# SCH_task_B_2026-06-26.net
KiCad netlist of a schematic drawn in EasyEDA
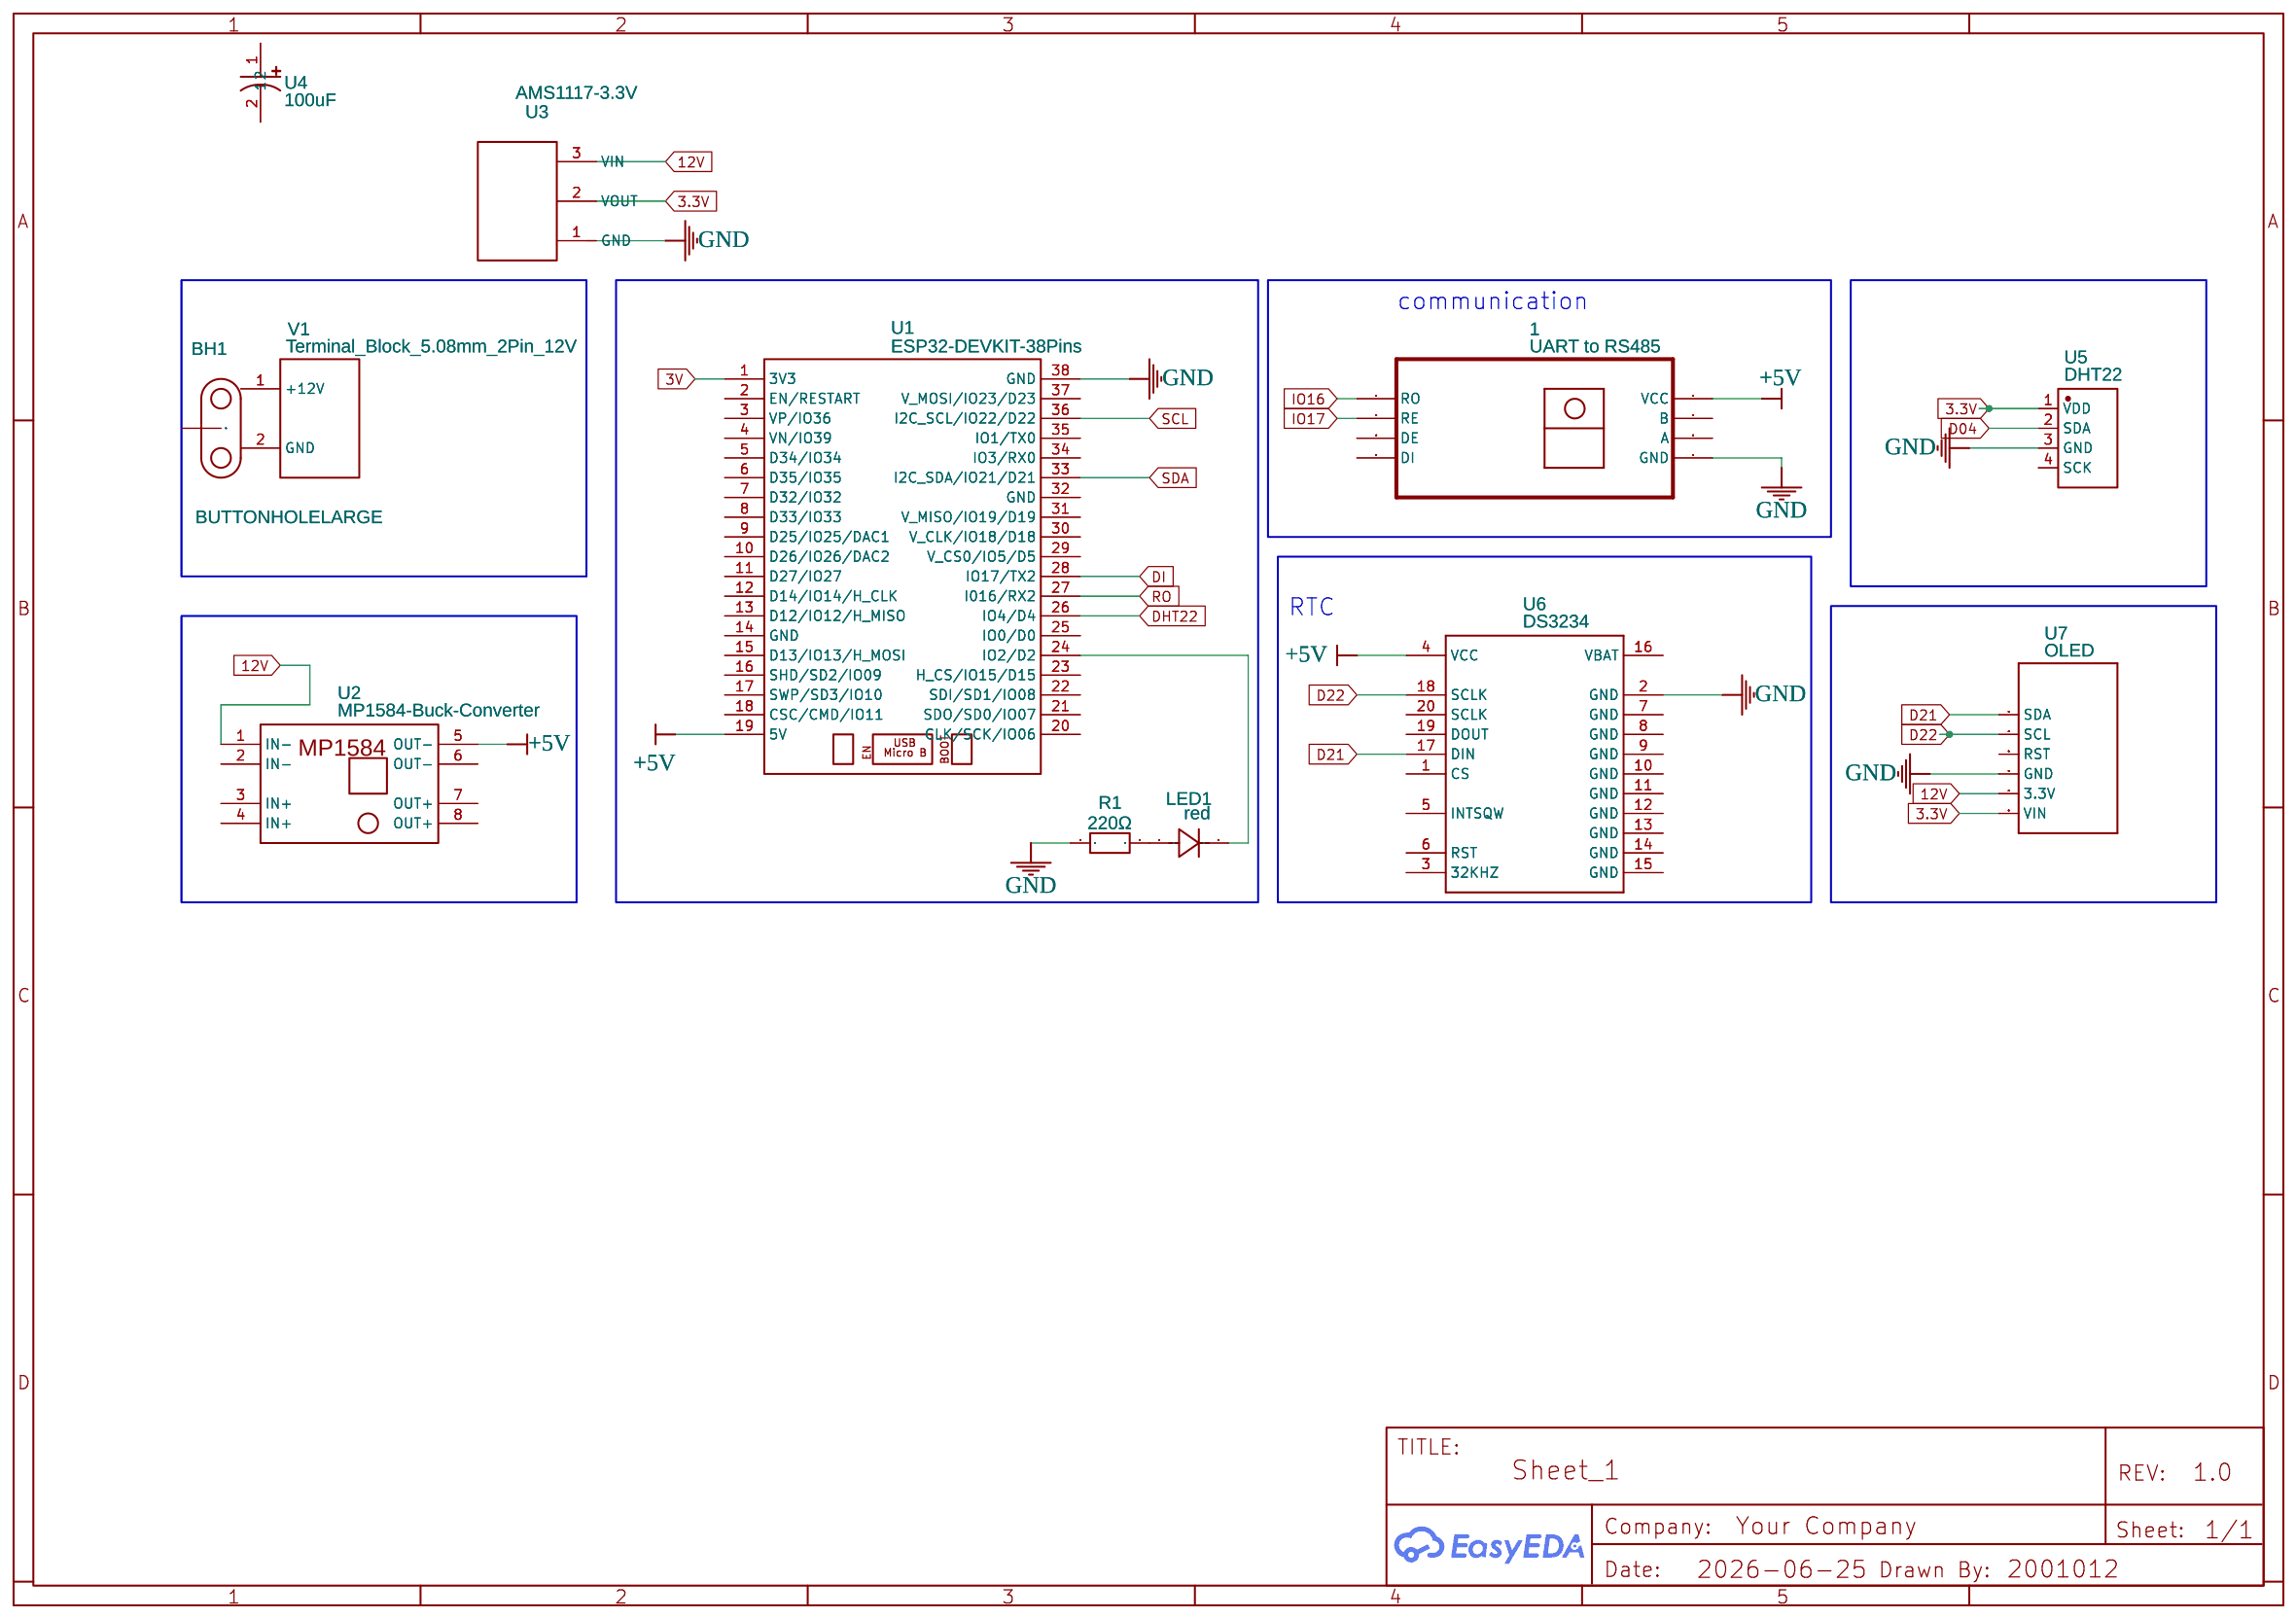
[diagram p0: schematic sheet]

(export (version "E")
  (design (tool "Eeschema 10.0.6"))
  (components
    (comp (ref "1") (value "UART to RS485") (libsource (lib "") (part "UART to RS485")))
    (comp (ref "BH1") (value "BUTTONHOLELARGE") (libsource (lib "") (part "BUTTONHOLELARGE")))
    (comp (ref "LED1")
      (value "red")
      (fields (field (name "Manufacturer Part") "YLED0402O") (field (name "Manufacturer") "YONGYUTAI(永裕泰)"))
      (libsource (lib "") (part "YLED0402O"))
    )
    (comp (ref "R1")
      (value "220Ω")
      (fields (field (name "Manufacturer Part") "RWS10 220R J TR") (field (name "Manufacturer") "Ohmite"))
      (libsource (lib "") (part "RWS10 220R J TR"))
    )
    (comp (ref "U1") (value "ESP32-DEVKIT-38Pins") (libsource (lib "") (part "ESP32-DEVKIT-38Pins")))
    (comp (ref "U2")
      (value "MP1584-Buck-Converter")
      (fields (field (name "Manufacturer Part") "MP1584EN"))
      (libsource (lib "") (part "MP1584-Buck-Converter"))
    )
    (comp (ref "U3") (value "AMS1117-3.3V") (libsource (lib "") (part "AMS1117-3.3V")))
    (comp (ref "U4")
      (value "100uF")
      (fields
        (field (name "Manufacturer Part") "6.3NA100MEFC5X11")
        (field (name "Manufacturer") "rubycon(红宝石)")
      )
      (libsource (lib "") (part "100UF-D5XL11MM-HORN-TYPE-POLAR-ELECTROLYTIC-CAPACITORS COPY"))
    )
    (comp (ref "U5")
      (value "DHT22")
      (fields (field (name "Manufacturer") "HAIGU(广州海谷)"))
      (libsource (lib "") (part "DHT22"))
    )
    (comp (ref "U6") (value "DS3234") (libsource (lib "") (part "DS3234")))
    (comp (ref "U7") (value "OLED") (libsource (lib "") (part "ADAFRUIT_128X32_OLED")))
    (comp (ref "V1")
      (value "Terminal_Block_5.08mm_2Pin_12V")
      (libsource (lib "") (part "Terminal_Block_5.08mm_2Pin_12V"))
    )
  )
  (nets
    (net (code "1") (name "+5V") (class "Default")
      (node (ref "1") (pin "RS5") (pinfunction "VCC_RS5") (pintype "bidirectional"))
      (node (ref "U1") (pin "19") (pinfunction "5V_19") (pintype "unspecified"))
      (node (ref "U2") (pin "5") (pinfunction "OUT-_5") (pintype "unspecified"))
      (node (ref "U6") (pin "4") (pinfunction "VCC_4") (pintype "unspecified"))
    )
    (net (code "2") (name "3.3V") (class "Default")
      (node (ref "U5") (pin "1") (pinfunction "VDD_1") (pintype "unspecified"))
      (node (ref "U7") (pin "P$6") (pinfunction "VIN_P$6") (pintype "passive"))
    )
    (net (code "3") (name "3V") (class "Default")
      (node (ref "U1") (pin "1") (pinfunction "3V3_1") (pintype "unspecified"))
    )
    (net (code "4") (name "12V") (class "Default")
      (node (ref "U2") (pin "1") (pinfunction "IN-_1") (pintype "unspecified"))
      (node (ref "U7") (pin "P$5") (pinfunction "3.3V_P$5") (pintype "passive"))
    )
    (net (code "5") (name "D04") (class "Default")
      (node (ref "U5") (pin "2") (pinfunction "SDA_2") (pintype "unspecified"))
    )
    (net (code "6") (name "D21") (class "Default")
      (node (ref "U6") (pin "17") (pinfunction "DIN_17") (pintype "unspecified"))
      (node (ref "U7") (pin "P$1") (pinfunction "SDA_P$1") (pintype "unspecified"))
    )
    (net (code "7") (name "D22") (class "Default")
      (node (ref "U6") (pin "18") (pinfunction "SCLK_18") (pintype "unspecified"))
      (node (ref "U7") (pin "P$2") (pinfunction "SCL_P$2") (pintype "unspecified"))
    )
    (net (code "8") (name "DHT22") (class "Default")
      (node (ref "U1") (pin "26") (pinfunction "IO4/D4_26") (pintype "unspecified"))
    )
    (net (code "9") (name "DI") (class "Default")
      (node (ref "U1") (pin "28") (pinfunction "IO17/TX2_28") (pintype "unspecified"))
    )
    (net (code "10") (name "GND") (class "Default")
      (node (ref "1") (pin "RS8") (pinfunction "GND_RS8") (pintype "bidirectional"))
      (node (ref "R1") (pin "1") (pinfunction "1_1") (pintype "unspecified"))
      (node (ref "U1") (pin "38") (pinfunction "GND_38") (pintype "unspecified"))
      (node (ref "U5") (pin "3") (pinfunction "GND_3") (pintype "unspecified"))
      (node (ref "U6") (pin "2") (pinfunction "GND_2") (pintype "unspecified"))
      (node (ref "U7") (pin "P$4") (pinfunction "GND_P$4") (pintype "passive"))
    )
    (net (code "11") (name "IO16") (class "Default")
      (node (ref "1") (pin "RS1") (pinfunction "RO_RS1") (pintype "bidirectional"))
    )
    (net (code "12") (name "IO17") (class "Default")
      (node (ref "1") (pin "RS2") (pinfunction "RE_RS2") (pintype "bidirectional"))
    )
    (net (code "13") (name "Net-(LED1-A)") (class "Default")
      (node (ref "LED1") (pin "1") (pinfunction "A_1") (pintype "unspecified"))
      (node (ref "R1") (pin "2") (pinfunction "2_2") (pintype "unspecified"))
    )
    (net (code "14") (name "Net-(LED1-C)") (class "Default")
      (node (ref "LED1") (pin "2") (pinfunction "C_2") (pintype "unspecified"))
      (node (ref "U1") (pin "24") (pinfunction "IO2/D2_24") (pintype "unspecified"))
    )
    (net (code "15") (name "RO") (class "Default")
      (node (ref "U1") (pin "27") (pinfunction "I016/RX2_27") (pintype "unspecified"))
    )
    (net (code "16") (name "SCL") (class "Default")
      (node (ref "U1") (pin "36") (pinfunction "I2C_SCL/IO22/D22_36") (pintype "unspecified"))
    )
    (net (code "17") (name "SDA") (class "Default")
      (node (ref "U1") (pin "33") (pinfunction "I2C_SDA/IO21/D21_33") (pintype "unspecified"))
    )
    (net (code "18") (name "unconnected-(1-A-PadRS7)") (class "Default")
      (node (ref "1") (pin "RS7") (pinfunction "A_RS7") (pintype "bidirectional"))
    )
    (net (code "19") (name "unconnected-(1-B-PadRS6)") (class "Default")
      (node (ref "1") (pin "RS6") (pinfunction "B_RS6") (pintype "bidirectional"))
    )
    (net (code "20") (name "unconnected-(1-DE-PadRS3)") (class "Default")
      (node (ref "1") (pin "RS3") (pinfunction "DE_RS3") (pintype "bidirectional"))
    )
    (net (code "21") (name "unconnected-(1-DI-PadRS4)") (class "Default")
      (node (ref "1") (pin "RS4") (pinfunction "DI_RS4") (pintype "bidirectional"))
    )
    (net (code "22") (name "unconnected-(BH1-PadP$1)") (class "Default")
      (node (ref "BH1") (pin "P$1") (pinfunction "P$1_P$1") (pintype "unspecified"))
    )
    (net (code "23") (name "unconnected-(U1-CLK{slash}SCK{slash}IO06-Pad20)") (class "Default")
      (node (ref "U1") (pin "20") (pinfunction "CLK/SCK/IO06_20") (pintype "unspecified"))
    )
    (net (code "24") (name "unconnected-(U1-CSC{slash}CMD{slash}IO11-Pad18)") (class "Default")
      (node (ref "U1") (pin "18") (pinfunction "CSC/CMD/IO11_18") (pintype "unspecified"))
    )
    (net (code "25") (name "unconnected-(U1-D12{slash}IO12{slash}H_MISO-Pad13)") (class "Default")
      (node (ref "U1") (pin "13") (pinfunction "D12/IO12/H_MISO_13") (pintype "unspecified"))
    )
    (net (code "26") (name "unconnected-(U1-D13{slash}IO13{slash}H_MOSI-Pad15)") (class "Default")
      (node (ref "U1") (pin "15") (pinfunction "D13/IO13/H_MOSI_15") (pintype "unspecified"))
    )
    (net (code "27") (name "unconnected-(U1-D14{slash}IO14{slash}H_CLK-Pad12)") (class "Default")
      (node (ref "U1") (pin "12") (pinfunction "D14/IO14/H_CLK_12") (pintype "unspecified"))
    )
    (net (code "28") (name "unconnected-(U1-D25{slash}IO25{slash}DAC1-Pad9)") (class "Default")
      (node (ref "U1") (pin "9") (pinfunction "D25/IO25/DAC1_9") (pintype "unspecified"))
    )
    (net (code "29") (name "unconnected-(U1-D26{slash}IO26{slash}DAC2-Pad10)") (class "Default")
      (node (ref "U1") (pin "10") (pinfunction "D26/IO26/DAC2_10") (pintype "unspecified"))
    )
    (net (code "30") (name "unconnected-(U1-D27{slash}IO27-Pad11)") (class "Default")
      (node (ref "U1") (pin "11") (pinfunction "D27/IO27_11") (pintype "unspecified"))
    )
    (net (code "31") (name "unconnected-(U1-D32{slash}IO32-Pad7)") (class "Default")
      (node (ref "U1") (pin "7") (pinfunction "D32/IO32_7") (pintype "unspecified"))
    )
    (net (code "32") (name "unconnected-(U1-D33{slash}IO33-Pad8)") (class "Default")
      (node (ref "U1") (pin "8") (pinfunction "D33/IO33_8") (pintype "unspecified"))
    )
    (net (code "33") (name "unconnected-(U1-D34{slash}IO34-Pad5)") (class "Default")
      (node (ref "U1") (pin "5") (pinfunction "D34/IO34_5") (pintype "unspecified"))
    )
    (net (code "34") (name "unconnected-(U1-D35{slash}IO35-Pad6)") (class "Default")
      (node (ref "U1") (pin "6") (pinfunction "D35/IO35_6") (pintype "unspecified"))
    )
    (net (code "35") (name "unconnected-(U1-EN{slash}RESTART-Pad2)") (class "Default")
      (node (ref "U1") (pin "2") (pinfunction "EN/RESTART_2") (pintype "unspecified"))
    )
    (net (code "36") (name "unconnected-(U1-GND-Pad14)") (class "Default")
      (node (ref "U1") (pin "14") (pinfunction "GND_14") (pintype "unspecified"))
    )
    (net (code "37") (name "unconnected-(U1-GND-Pad32)") (class "Default")
      (node (ref "U1") (pin "32") (pinfunction "GND_32") (pintype "unspecified"))
    )
    (net (code "38") (name "unconnected-(U1-H_CS{slash}IO15{slash}D15-Pad23)") (class "Default")
      (node (ref "U1") (pin "23") (pinfunction "H_CS/IO15/D15_23") (pintype "unspecified"))
    )
    (net (code "39") (name "unconnected-(U1-IO0{slash}D0-Pad25)") (class "Default")
      (node (ref "U1") (pin "25") (pinfunction "IO0/D0_25") (pintype "unspecified"))
    )
    (net (code "40") (name "unconnected-(U1-IO1{slash}TX0-Pad35)") (class "Default")
      (node (ref "U1") (pin "35") (pinfunction "IO1/TX0_35") (pintype "unspecified"))
    )
    (net (code "41") (name "unconnected-(U1-IO3{slash}RX0-Pad34)") (class "Default")
      (node (ref "U1") (pin "34") (pinfunction "IO3/RX0_34") (pintype "unspecified"))
    )
    (net (code "42") (name "unconnected-(U1-SDI{slash}SD1{slash}IO08-Pad22)") (class "Default")
      (node (ref "U1") (pin "22") (pinfunction "SDI/SD1/IO08_22") (pintype "unspecified"))
    )
    (net (code "43") (name "unconnected-(U1-SDO{slash}SD0{slash}IO07-Pad21)") (class "Default")
      (node (ref "U1") (pin "21") (pinfunction "SDO/SD0/IO07_21") (pintype "unspecified"))
    )
    (net (code "44") (name "unconnected-(U1-SHD{slash}SD2{slash}IO09-Pad16)") (class "Default")
      (node (ref "U1") (pin "16") (pinfunction "SHD/SD2/IO09_16") (pintype "unspecified"))
    )
    (net (code "45") (name "unconnected-(U1-SWP{slash}SD3{slash}IO10-Pad17)") (class "Default")
      (node (ref "U1") (pin "17") (pinfunction "SWP/SD3/IO10_17") (pintype "unspecified"))
    )
    (net (code "46") (name "unconnected-(U1-VN{slash}IO39-Pad4)") (class "Default")
      (node (ref "U1") (pin "4") (pinfunction "VN/IO39_4") (pintype "unspecified"))
    )
    (net (code "47") (name "unconnected-(U1-VP{slash}IO36-Pad3)") (class "Default")
      (node (ref "U1") (pin "3") (pinfunction "VP/IO36_3") (pintype "unspecified"))
    )
    (net (code "48") (name "unconnected-(U1-V_CLK{slash}IO18{slash}D18-Pad30)") (class "Default")
      (node (ref "U1") (pin "30") (pinfunction "V_CLK/IO18/D18_30") (pintype "unspecified"))
    )
    (net (code "49") (name "unconnected-(U1-V_CS0{slash}IO5{slash}D5-Pad29)") (class "Default")
      (node (ref "U1") (pin "29") (pinfunction "V_CS0/IO5/D5_29") (pintype "unspecified"))
    )
    (net (code "50") (name "unconnected-(U1-V_MISO{slash}IO19{slash}D19-Pad31)") (class "Default")
      (node (ref "U1") (pin "31") (pinfunction "V_MISO/IO19/D19_31") (pintype "unspecified"))
    )
    (net (code "51") (name "unconnected-(U1-V_MOSI{slash}IO23{slash}D23-Pad37)") (class "Default")
      (node (ref "U1") (pin "37") (pinfunction "V_MOSI/IO23/D23_37") (pintype "unspecified"))
    )
    (net (code "52") (name "unconnected-(U2-IN+-Pad3)") (class "Default")
      (node (ref "U2") (pin "3") (pinfunction "IN+_3") (pintype "unspecified"))
    )
    (net (code "53") (name "unconnected-(U2-IN+-Pad4)") (class "Default")
      (node (ref "U2") (pin "4") (pinfunction "IN+_4") (pintype "unspecified"))
    )
    (net (code "54") (name "unconnected-(U2-IN--Pad2)") (class "Default")
      (node (ref "U2") (pin "2") (pinfunction "IN-_2") (pintype "unspecified"))
    )
    (net (code "55") (name "unconnected-(U2-OUT+-Pad7)") (class "Default")
      (node (ref "U2") (pin "7") (pinfunction "OUT+_7") (pintype "unspecified"))
    )
    (net (code "56") (name "unconnected-(U2-OUT+-Pad8)") (class "Default")
      (node (ref "U2") (pin "8") (pinfunction "OUT+_8") (pintype "unspecified"))
    )
    (net (code "57") (name "unconnected-(U2-OUT--Pad6)") (class "Default")
      (node (ref "U2") (pin "6") (pinfunction "OUT-_6") (pintype "unspecified"))
    )
    (net (code "58") (name "unconnected-(U3-GND-Pad1)") (class "Default")
      (node (ref "U3") (pin "1") (pinfunction "GND_1") (pintype "unspecified"))
    )
    (net (code "59") (name "unconnected-(U3-VIN-Pad3)") (class "Default")
      (node (ref "U3") (pin "3") (pinfunction "VIN_3") (pintype "unspecified"))
    )
    (net (code "60") (name "unconnected-(U3-VOUT-Pad2)") (class "Default")
      (node (ref "U3") (pin "2") (pinfunction "VOUT_2") (pintype "unspecified"))
    )
    (net (code "61") (name "unconnected-(U4-Pad1)") (class "Default")
      (node (ref "U4") (pin "1") (pinfunction "1_1") (pintype "unspecified"))
    )
    (net (code "62") (name "unconnected-(U4-Pad2)") (class "Default")
      (node (ref "U4") (pin "2") (pinfunction "2_2") (pintype "unspecified"))
    )
    (net (code "63") (name "unconnected-(U5-SCK-Pad4)") (class "Default")
      (node (ref "U5") (pin "4") (pinfunction "SCK_4") (pintype "unspecified"))
    )
    (net (code "64") (name "unconnected-(U6-32KHZ-Pad3)") (class "Default")
      (node (ref "U6") (pin "3") (pinfunction "32KHZ_3") (pintype "unspecified"))
    )
    (net (code "65") (name "unconnected-(U6-CS-Pad1)") (class "Default")
      (node (ref "U6") (pin "1") (pinfunction "CS_1") (pintype "unspecified"))
    )
    (net (code "66") (name "unconnected-(U6-DOUT-Pad19)") (class "Default")
      (node (ref "U6") (pin "19") (pinfunction "DOUT_19") (pintype "unspecified"))
    )
    (net (code "67") (name "unconnected-(U6-GND-Pad7)") (class "Default")
      (node (ref "U6") (pin "7") (pinfunction "GND_7") (pintype "unspecified"))
    )
    (net (code "68") (name "unconnected-(U6-GND-Pad8)") (class "Default")
      (node (ref "U6") (pin "8") (pinfunction "GND_8") (pintype "unspecified"))
    )
    (net (code "69") (name "unconnected-(U6-GND-Pad9)") (class "Default")
      (node (ref "U6") (pin "9") (pinfunction "GND_9") (pintype "unspecified"))
    )
    (net (code "70") (name "unconnected-(U6-GND-Pad10)") (class "Default")
      (node (ref "U6") (pin "10") (pinfunction "GND_10") (pintype "unspecified"))
    )
    (net (code "71") (name "unconnected-(U6-GND-Pad11)") (class "Default")
      (node (ref "U6") (pin "11") (pinfunction "GND_11") (pintype "unspecified"))
    )
    (net (code "72") (name "unconnected-(U6-GND-Pad12)") (class "Default")
      (node (ref "U6") (pin "12") (pinfunction "GND_12") (pintype "unspecified"))
    )
    (net (code "73") (name "unconnected-(U6-GND-Pad13)") (class "Default")
      (node (ref "U6") (pin "13") (pinfunction "GND_13") (pintype "unspecified"))
    )
    (net (code "74") (name "unconnected-(U6-GND-Pad14)") (class "Default")
      (node (ref "U6") (pin "14") (pinfunction "GND_14") (pintype "unspecified"))
    )
    (net (code "75") (name "unconnected-(U6-GND-Pad15)") (class "Default")
      (node (ref "U6") (pin "15") (pinfunction "GND_15") (pintype "unspecified"))
    )
    (net (code "76") (name "unconnected-(U6-INTSQW-Pad5)") (class "Default")
      (node (ref "U6") (pin "5") (pinfunction "INTSQW_5") (pintype "unspecified"))
    )
    (net (code "77") (name "unconnected-(U6-RST-Pad6)") (class "Default")
      (node (ref "U6") (pin "6") (pinfunction "RST_6") (pintype "unspecified"))
    )
    (net (code "78") (name "unconnected-(U6-SCLK-Pad20)") (class "Default")
      (node (ref "U6") (pin "20") (pinfunction "SCLK_20") (pintype "unspecified"))
    )
    (net (code "79") (name "unconnected-(U6-VBAT-Pad16)") (class "Default")
      (node (ref "U6") (pin "16") (pinfunction "VBAT_16") (pintype "unspecified"))
    )
    (net (code "80") (name "unconnected-(U7-RST-PadP$3)") (class "Default")
      (node (ref "U7") (pin "P$3") (pinfunction "RST_P$3") (pintype "input"))
    )
    (net (code "81") (name "unconnected-(V1-+12V-Pad1)") (class "Default")
      (node (ref "V1") (pin "1") (pinfunction "+12V_1") (pintype "unspecified"))
    )
    (net (code "82") (name "unconnected-(V1-GND-Pad2)") (class "Default")
      (node (ref "V1") (pin "2") (pinfunction "GND_2") (pintype "unspecified"))
    )
  )
)
